# VF_MDS_PCB.net
KiCad netlist of a schematic drawn in EAGLE
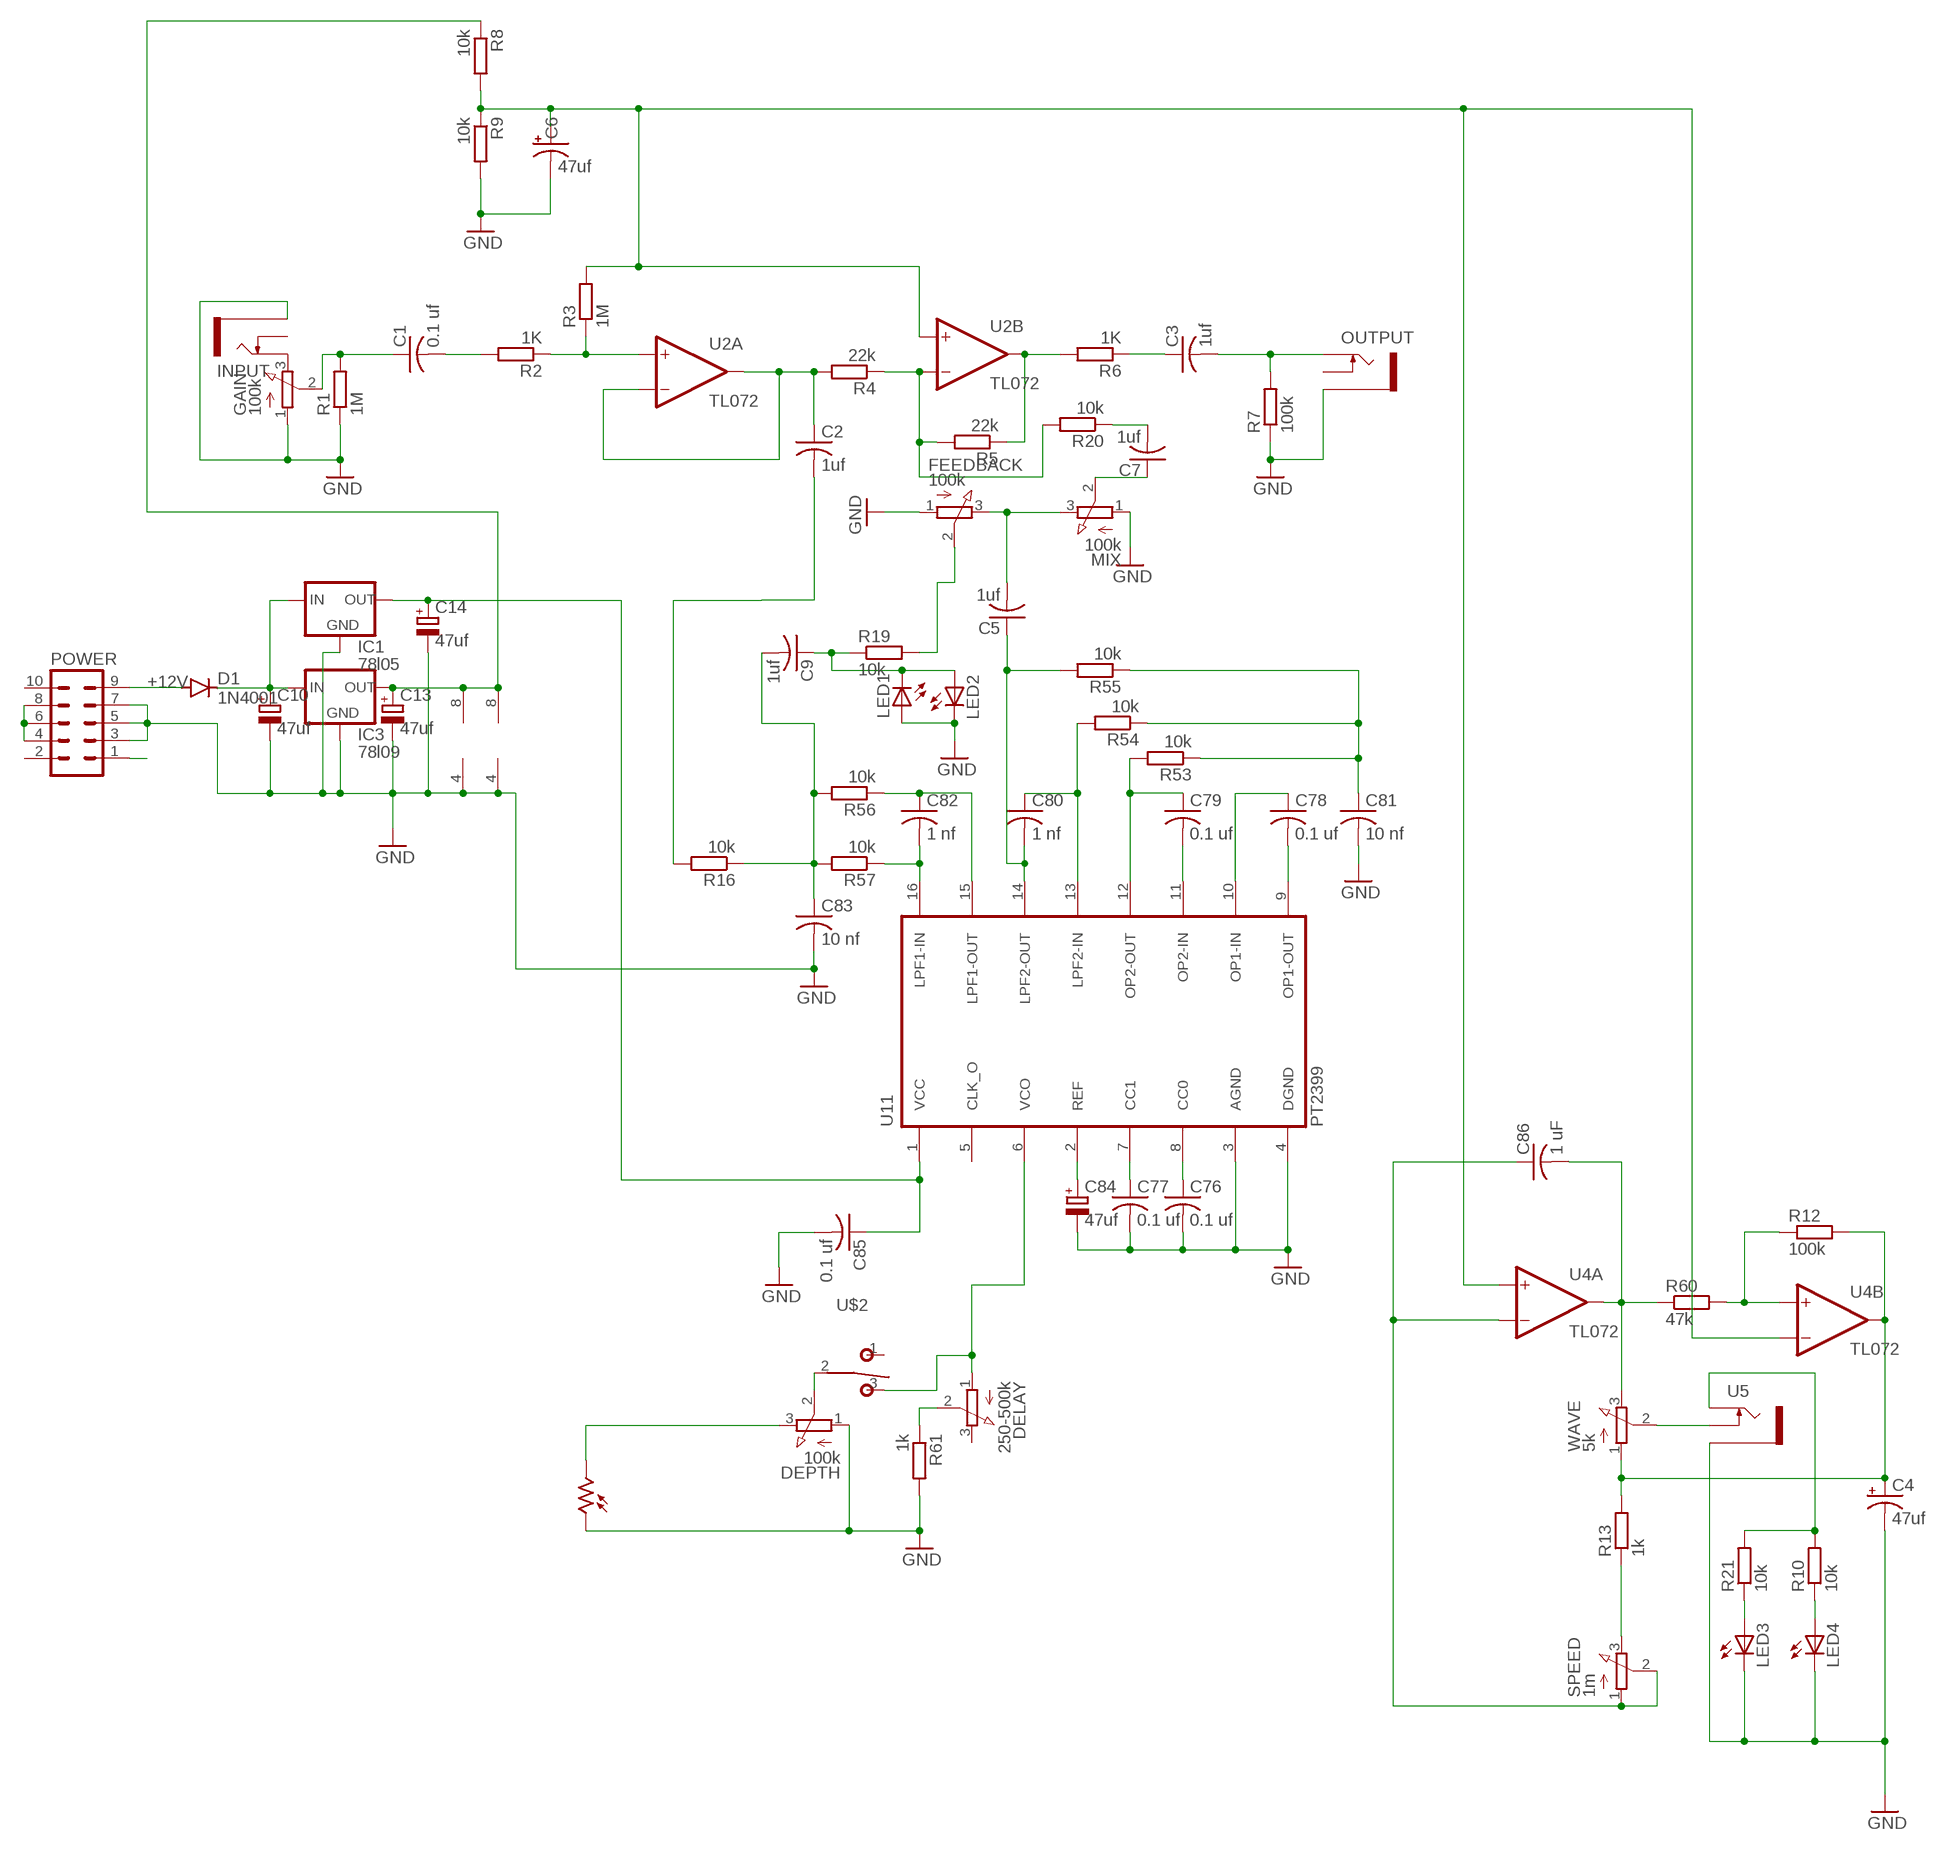
[diagram p0: schematic, sheet 1]

(export (version "E")
  (design (tool "Eeschema 10.0.6"))
  (components
    (comp (ref "C1")
      (value "0.1 uf")
      (footprint "eagle-import:C050-025X075")
      (libsource (lib "eagle-import") (part "C-US050-025X075"))
    )
    (comp (ref "C2")
      (value "1uf")
      (footprint "eagle-import:C050-025X075")
      (libsource (lib "eagle-import") (part "C-US050-025X075"))
    )
    (comp (ref "C3")
      (value "1uf")
      (footprint "eagle-import:C050-025X075")
      (libsource (lib "eagle-import") (part "C-US050-025X075"))
    )
    (comp (ref "C4")
      (value "47uf")
      (footprint "eagle-import:E2,5-6E")
      (libsource (lib "eagle-import") (part "CPOL-USE2,5-6E"))
    )
    (comp (ref "C5")
      (value "1uf")
      (footprint "eagle-import:C050-025X075")
      (libsource (lib "eagle-import") (part "C-US050-025X075"))
    )
    (comp (ref "C6")
      (value "47uf")
      (footprint "eagle-import:E2,5-6E")
      (libsource (lib "eagle-import") (part "CPOL-USE2,5-6E"))
    )
    (comp (ref "C7")
      (value "1uf")
      (footprint "eagle-import:C050-025X075")
      (libsource (lib "eagle-import") (part "C-US050-025X075"))
    )
    (comp (ref "C9")
      (value "1uf")
      (footprint "eagle-import:C050-025X075")
      (libsource (lib "eagle-import") (part "C-US050-025X075"))
    )
    (comp (ref "C10")
      (value "47uf")
      (footprint "eagle-import:E2,5-6E")
      (libsource (lib "eagle-import") (part "CPOL-EUE2,5-6E"))
    )
    (comp (ref "C13")
      (value "47uf")
      (footprint "eagle-import:E2,5-6E")
      (libsource (lib "eagle-import") (part "CPOL-EUE2,5-6E"))
    )
    (comp (ref "C14")
      (value "47uf")
      (footprint "eagle-import:E2,5-6E")
      (libsource (lib "eagle-import") (part "CPOL-EUE2,5-6E"))
    )
    (comp (ref "C76")
      (value "0.1 uf")
      (footprint "eagle-import:C050-025X075")
      (libsource (lib "eagle-import") (part "C-US050-025X075"))
    )
    (comp (ref "C77")
      (value "0.1 uf")
      (footprint "eagle-import:C050-025X075")
      (libsource (lib "eagle-import") (part "C-US050-025X075"))
    )
    (comp (ref "C78")
      (value "0.1 uf")
      (footprint "eagle-import:C050-025X075")
      (libsource (lib "eagle-import") (part "C-US050-025X075"))
    )
    (comp (ref "C79")
      (value "0.1 uf")
      (footprint "eagle-import:C050-025X075")
      (libsource (lib "eagle-import") (part "C-US050-025X075"))
    )
    (comp (ref "C80")
      (value "1 nf")
      (footprint "eagle-import:C050-025X075")
      (libsource (lib "eagle-import") (part "C-US050-025X075"))
    )
    (comp (ref "C81")
      (value "10 nf")
      (footprint "eagle-import:C050-025X075")
      (libsource (lib "eagle-import") (part "C-US050-025X075"))
    )
    (comp (ref "C82")
      (value "1 nf")
      (footprint "eagle-import:C050-025X075")
      (libsource (lib "eagle-import") (part "C-US050-025X075"))
    )
    (comp (ref "C83")
      (value "10 nf")
      (footprint "eagle-import:C050-025X075")
      (libsource (lib "eagle-import") (part "C-US050-025X075"))
    )
    (comp (ref "C84")
      (value "47uf")
      (footprint "eagle-import:E2,5-6E")
      (libsource (lib "eagle-import") (part "CPOL-EUE2,5-6E"))
    )
    (comp (ref "C85")
      (value "0.1 uf")
      (footprint "eagle-import:C050-025X075")
      (libsource (lib "eagle-import") (part "C-US050-025X075"))
    )
    (comp (ref "C86")
      (value "1 uF")
      (footprint "eagle-import:C050-025X075")
      (libsource (lib "eagle-import") (part "C-US050-025X075"))
    )
    (comp (ref "D1")
      (value "1N4001")
      (footprint "eagle-import:DO41-10")
      (libsource (lib "eagle-import") (part "1N4004"))
    )
    (comp (ref "DELAY")
      (value "250-500k")
      (footprint "eagle-import:EVUFXL")
      (libsource (lib "eagle-import") (part "EVULF2"))
    )
    (comp (ref "DEPTH")
      (value "100k")
      (footprint "eagle-import:EVUFXL")
      (libsource (lib "eagle-import") (part "EVULF2"))
    )
    (comp (ref "FEEDBACK")
      (value "100k")
      (footprint "eagle-import:EVUFXL")
      (libsource (lib "eagle-import") (part "EVULF2"))
    )
    (comp (ref "GAIN")
      (value "100k")
      (footprint "eagle-import:EVUFXL")
      (libsource (lib "eagle-import") (part "EVULF2"))
    )
    (comp (ref "IC1")
      (value "78l05")
      (footprint "eagle-import:78LXX")
      (libsource (lib "eagle-import") (part "78LXX"))
    )
    (comp (ref "IC3")
      (value "78l09")
      (footprint "eagle-import:78LXX")
      (libsource (lib "eagle-import") (part "78LXX"))
    )
    (comp (ref "INPUT")
      (value "THONKICONNNEW")
      (footprint "eagle-import:WQP-PJ301M-12_JACK")
      (libsource (lib "eagle-import") (part "THONKICONNNEW"))
    )
    (comp (ref "LED1")
      (value "LED3MM")
      (footprint "eagle-import:LED3MM")
      (libsource (lib "eagle-import") (part "LED3MM"))
    )
    (comp (ref "LED2")
      (value "LED3MM")
      (footprint "eagle-import:LED3MM")
      (libsource (lib "eagle-import") (part "LED3MM"))
    )
    (comp (ref "LED3")
      (value "LED5MM")
      (footprint "eagle-import:LED5MM")
      (libsource (lib "eagle-import") (part "LED5MM"))
    )
    (comp (ref "LED4")
      (value "LED5MM")
      (footprint "eagle-import:LED5MM")
      (libsource (lib "eagle-import") (part "LED5MM"))
    )
    (comp (ref "MIX")
      (value "100k")
      (footprint "eagle-import:EVUFXL")
      (libsource (lib "eagle-import") (part "EVULF2"))
    )
    (comp (ref "OUTPUT")
      (value "THONKICONNNEW")
      (footprint "eagle-import:WQP-PJ301M-12_JACK")
      (libsource (lib "eagle-import") (part "THONKICONNNEW"))
    )
    (comp (ref "PH5")
      (value "VT90N1")
      (footprint "eagle-import:VT900")
      (libsource (lib "eagle-import") (part "VT90N1"))
    )
    (comp (ref "POWER")
      (value "10_PIN_HEADER")
      (footprint "eagle-import:MA05-2")
      (libsource (lib "eagle-import") (part "10_PIN_HEADER"))
    )
    (comp (ref "R1")
      (value "1M")
      (footprint "eagle-import:7MM_RESISTOR")
      (libsource (lib "eagle-import") (part "RESISTOR7MM"))
    )
    (comp (ref "R2")
      (value "1K")
      (footprint "eagle-import:7MM_RESISTOR")
      (libsource (lib "eagle-import") (part "RESISTOR7MM"))
    )
    (comp (ref "R3")
      (value "1M")
      (footprint "eagle-import:7MM_RESISTOR")
      (libsource (lib "eagle-import") (part "RESISTOR7MM"))
    )
    (comp (ref "R4")
      (value "22k")
      (footprint "eagle-import:7MM_RESISTOR")
      (libsource (lib "eagle-import") (part "RESISTOR7MM"))
    )
    (comp (ref "R5")
      (value "22k")
      (footprint "eagle-import:7MM_RESISTOR")
      (libsource (lib "eagle-import") (part "RESISTOR7MM"))
    )
    (comp (ref "R6")
      (value "1K")
      (footprint "eagle-import:7MM_RESISTOR")
      (libsource (lib "eagle-import") (part "RESISTOR7MM"))
    )
    (comp (ref "R7")
      (value "100k")
      (footprint "eagle-import:7MM_RESISTOR")
      (libsource (lib "eagle-import") (part "RESISTOR7MM"))
    )
    (comp (ref "R8")
      (value "10k")
      (footprint "eagle-import:7MM_RESISTOR")
      (libsource (lib "eagle-import") (part "RESISTOR7MM"))
    )
    (comp (ref "R9")
      (value "10k")
      (footprint "eagle-import:7MM_RESISTOR")
      (libsource (lib "eagle-import") (part "RESISTOR7MM"))
    )
    (comp (ref "R10")
      (value "10k")
      (footprint "eagle-import:7MM_RESISTOR")
      (libsource (lib "eagle-import") (part "RESISTOR7MM"))
    )
    (comp (ref "R12")
      (value "100k")
      (footprint "eagle-import:7MM_RESISTOR")
      (libsource (lib "eagle-import") (part "RESISTOR7MM"))
    )
    (comp (ref "R13")
      (value "1k")
      (footprint "eagle-import:7MM_RESISTOR")
      (libsource (lib "eagle-import") (part "RESISTOR7MM"))
    )
    (comp (ref "R16")
      (value "10k")
      (footprint "eagle-import:7MM_RESISTOR")
      (libsource (lib "eagle-import") (part "RESISTOR7MM"))
    )
    (comp (ref "R19")
      (value "10k")
      (footprint "eagle-import:7MM_RESISTOR")
      (libsource (lib "eagle-import") (part "RESISTOR7MM"))
    )
    (comp (ref "R20")
      (value "10k")
      (footprint "eagle-import:7MM_RESISTOR")
      (libsource (lib "eagle-import") (part "RESISTOR7MM"))
    )
    (comp (ref "R21")
      (value "10k")
      (footprint "eagle-import:7MM_RESISTOR")
      (libsource (lib "eagle-import") (part "RESISTOR7MM"))
    )
    (comp (ref "R53")
      (value "10k")
      (footprint "eagle-import:7MM_RESISTOR")
      (libsource (lib "eagle-import") (part "RESISTOR7MM"))
    )
    (comp (ref "R54")
      (value "10k")
      (footprint "eagle-import:7MM_RESISTOR")
      (libsource (lib "eagle-import") (part "RESISTOR7MM"))
    )
    (comp (ref "R55")
      (value "10k")
      (footprint "eagle-import:7MM_RESISTOR")
      (libsource (lib "eagle-import") (part "RESISTOR7MM"))
    )
    (comp (ref "R56")
      (value "10k")
      (footprint "eagle-import:7MM_RESISTOR")
      (libsource (lib "eagle-import") (part "RESISTOR7MM"))
    )
    (comp (ref "R57")
      (value "10k")
      (footprint "eagle-import:7MM_RESISTOR")
      (libsource (lib "eagle-import") (part "RESISTOR7MM"))
    )
    (comp (ref "R60")
      (value "47k")
      (footprint "eagle-import:7MM_RESISTOR")
      (libsource (lib "eagle-import") (part "RESISTOR7MM"))
    )
    (comp (ref "R61")
      (value "1k")
      (footprint "eagle-import:7MM_RESISTOR")
      (libsource (lib "eagle-import") (part "RESISTOR7MM"))
    )
    (comp (ref "SPEED")
      (value "1m")
      (footprint "eagle-import:EVUFXL")
      (libsource (lib "eagle-import") (part "EVULF2"))
    )
    (comp (ref "U$2")
      (value "T-80-T-SPDT-ON-OFF-ON")
      (footprint "eagle-import:M9040P")
      (libsource (lib "eagle-import") (part "T-80-T-SPDT-ON-OFF-ON"))
    )
    (comp (ref "U2")
      (value "TL072")
      (footprint "eagle-import:DIL08-SML")
      (libsource (lib "eagle-import") (part "TL072"))
    )
    (comp (ref "U4")
      (value "TL072")
      (footprint "eagle-import:DIL08-SML")
      (libsource (lib "eagle-import") (part "TL072"))
    )
    (comp (ref "U5")
      (value "THONKICONNNEW")
      (footprint "eagle-import:WQP-PJ301M-12_JACK")
      (libsource (lib "eagle-import") (part "THONKICONNNEW"))
    )
    (comp (ref "U11")
      (value "PT2399")
      (footprint "eagle-import:DIL16")
      (libsource (lib "eagle-import") (part "PT2399"))
    )
    (comp (ref "WAVE")
      (value "5k")
      (footprint "eagle-import:EVUFXL")
      (libsource (lib "eagle-import") (part "EVULF2"))
    )
  )
  (nets
    (net (code "1") (name "/+12V") (class "Default")
      (node (ref "C10") (pin "+") (pinfunction "+_+") (pintype "passive"))
      (node (ref "D1") (pin "C") (pinfunction "C_C") (pintype "passive"))
      (node (ref "IC1") (pin "IN") (pinfunction "IN_IN") (pintype "input"))
      (node (ref "IC3") (pin "IN") (pinfunction "IN_IN") (pintype "input"))
    )
    (net (code "2") (name "GND") (class "Default")
      (node (ref "C10") (pin "-") (pinfunction "-_-") (pintype "passive"))
      (node (ref "C13") (pin "-") (pinfunction "-_-") (pintype "passive"))
      (node (ref "C14") (pin "-") (pinfunction "-_-") (pintype "passive"))
      (node (ref "C4") (pin "-") (pinfunction "-_-") (pintype "passive"))
      (node (ref "C6") (pin "-") (pinfunction "-_-") (pintype "passive"))
      (node (ref "C76") (pin "2") (pinfunction "2_2") (pintype "passive"))
      (node (ref "C77") (pin "2") (pinfunction "2_2") (pintype "passive"))
      (node (ref "C81") (pin "2") (pinfunction "2_2") (pintype "passive"))
      (node (ref "C83") (pin "2") (pinfunction "2_2") (pintype "passive"))
      (node (ref "C84") (pin "-") (pinfunction "-_-") (pintype "passive"))
      (node (ref "C85") (pin "2") (pinfunction "2_2") (pintype "passive"))
      (node (ref "DEPTH") (pin "1") (pinfunction "A_1") (pintype "passive"))
      (node (ref "FEEDBACK") (pin "1") (pinfunction "A_1") (pintype "passive"))
      (node (ref "GAIN") (pin "1") (pinfunction "A_1") (pintype "passive"))
      (node (ref "IC1") (pin "GND") (pinfunction "GND_GND") (pintype "input"))
      (node (ref "IC3") (pin "GND") (pinfunction "GND_GND") (pintype "input"))
      (node (ref "INPUT") (pin "P$3_SLEEVE") (pinfunction "SLEEVE_P$3_SLEEVE") (pintype "passive"))
      (node (ref "LED1") (pin "A") (pinfunction "A_A") (pintype "passive"))
      (node (ref "LED2") (pin "K") (pinfunction "C_K") (pintype "passive"))
      (node (ref "LED3") (pin "K") (pinfunction "C_K") (pintype "passive"))
      (node (ref "LED4") (pin "K") (pinfunction "C_K") (pintype "passive"))
      (node (ref "MIX") (pin "1") (pinfunction "A_1") (pintype "passive"))
      (node (ref "OUTPUT") (pin "P$3_SLEEVE") (pinfunction "SLEEVE_P$3_SLEEVE") (pintype "passive"))
      (node (ref "PH5") (pin "1") (pinfunction "1_1") (pintype "passive"))
      (node (ref "POWER") (pin "3") (pinfunction "3_3") (pintype "passive"))
      (node (ref "POWER") (pin "5") (pinfunction "5_5") (pintype "passive"))
      (node (ref "POWER") (pin "7") (pinfunction "7_7") (pintype "passive"))
      (node (ref "R1") (pin "1") (pinfunction "1_1") (pintype "passive"))
      (node (ref "R61") (pin "2") (pinfunction "2_2") (pintype "passive"))
      (node (ref "R7") (pin "1") (pinfunction "1_1") (pintype "passive"))
      (node (ref "R9") (pin "2") (pinfunction "2_2") (pintype "passive"))
      (node (ref "U11") (pin "3") (pinfunction "AGND_3") (pintype "power_in"))
      (node (ref "U11") (pin "4") (pinfunction "DGND_4") (pintype "power_in"))
      (node (ref "U2") (pin "4") (pinfunction "V-_4") (pintype "power_in"))
      (node (ref "U4") (pin "4") (pinfunction "V-_4") (pintype "power_in"))
      (node (ref "U5") (pin "P$3_SLEEVE") (pinfunction "SLEEVE_P$3_SLEEVE") (pintype "passive"))
    )
    (net (code "3") (name "Net-(C1-Pad2)") (class "Default")
      (node (ref "C1") (pin "2") (pinfunction "2_2") (pintype "passive"))
      (node (ref "R2") (pin "2") (pinfunction "2_2") (pintype "passive"))
    )
    (net (code "4") (name "Net-(C2-Pad2)") (class "Default")
      (node (ref "C2") (pin "2") (pinfunction "2_2") (pintype "passive"))
      (node (ref "R16") (pin "2") (pinfunction "2_2") (pintype "passive"))
    )
    (net (code "5") (name "Net-(C3-Pad1)") (class "Default")
      (node (ref "C3") (pin "1") (pinfunction "1_1") (pintype "passive"))
      (node (ref "R6") (pin "1") (pinfunction "1_1") (pintype "passive"))
    )
    (net (code "6") (name "Net-(C7-Pad2)") (class "Default")
      (node (ref "C7") (pin "2") (pinfunction "2_2") (pintype "passive"))
      (node (ref "R20") (pin "1") (pinfunction "1_1") (pintype "passive"))
    )
    (net (code "7") (name "Net-(C81-Pad1)") (class "Default")
      (node (ref "C81") (pin "1") (pinfunction "1_1") (pintype "passive"))
      (node (ref "R53") (pin "1") (pinfunction "1_1") (pintype "passive"))
      (node (ref "R54") (pin "1") (pinfunction "1_1") (pintype "passive"))
      (node (ref "R55") (pin "1") (pinfunction "1_1") (pintype "passive"))
    )
    (net (code "8") (name "Net-(C83-Pad1)") (class "Default")
      (node (ref "C83") (pin "1") (pinfunction "1_1") (pintype "passive"))
      (node (ref "C9") (pin "2") (pinfunction "2_2") (pintype "passive"))
      (node (ref "R16") (pin "1") (pinfunction "1_1") (pintype "passive"))
      (node (ref "R56") (pin "2") (pinfunction "2_2") (pintype "passive"))
      (node (ref "R57") (pin "2") (pinfunction "2_2") (pintype "passive"))
    )
    (net (code "9") (name "Net-(D1-PadA)") (class "Default")
      (node (ref "D1") (pin "A") (pinfunction "A_A") (pintype "passive"))
      (node (ref "POWER") (pin "9") (pinfunction "9_9") (pintype "passive"))
    )
    (net (code "10") (name "Net-(DELAY-A)") (class "Default")
      (node (ref "DELAY") (pin "1") (pinfunction "A_1") (pintype "passive"))
      (node (ref "U$2") (pin "3") (pinfunction "S_3") (pintype "passive"))
      (node (ref "U11") (pin "6") (pinfunction "VCO_6") (pintype "input"))
    )
    (net (code "11") (name "Net-(DELAY-S)") (class "Default")
      (node (ref "DELAY") (pin "2") (pinfunction "S_2") (pintype "passive"))
      (node (ref "R61") (pin "1") (pinfunction "1_1") (pintype "passive"))
    )
    (net (code "12") (name "Net-(DEPTH-E)") (class "Default")
      (node (ref "DEPTH") (pin "3") (pinfunction "E_3") (pintype "passive"))
      (node (ref "PH5") (pin "2") (pinfunction "2_2") (pintype "passive"))
    )
    (net (code "13") (name "Net-(DEPTH-S)") (class "Default")
      (node (ref "DEPTH") (pin "2") (pinfunction "S_2") (pintype "passive"))
      (node (ref "U$2") (pin "2") (pinfunction "P_2") (pintype "passive"))
    )
    (net (code "14") (name "Net-(FEEDBACK-E)") (class "Default")
      (node (ref "C5") (pin "2") (pinfunction "2_2") (pintype "passive"))
      (node (ref "FEEDBACK") (pin "3") (pinfunction "E_3") (pintype "passive"))
      (node (ref "MIX") (pin "3") (pinfunction "E_3") (pintype "passive"))
    )
    (net (code "15") (name "Net-(FEEDBACK-S)") (class "Default")
      (node (ref "FEEDBACK") (pin "2") (pinfunction "S_2") (pintype "passive"))
      (node (ref "R19") (pin "2") (pinfunction "2_2") (pintype "passive"))
    )
    (net (code "16") (name "Net-(GAIN-E)") (class "Default")
      (node (ref "GAIN") (pin "3") (pinfunction "E_3") (pintype "passive"))
      (node (ref "INPUT") (pin "P$1_TIP") (pinfunction "TIP_P$1_TIP") (pintype "passive"))
    )
    (net (code "17") (name "Net-(GAIN-S)") (class "Default")
      (node (ref "C1") (pin "1") (pinfunction "1_1") (pintype "passive"))
      (node (ref "GAIN") (pin "2") (pinfunction "S_2") (pintype "passive"))
      (node (ref "R1") (pin "2") (pinfunction "2_2") (pintype "passive"))
    )
    (net (code "18") (name "Net-(LED1-C)") (class "Default")
      (node (ref "C9") (pin "1") (pinfunction "1_1") (pintype "passive"))
      (node (ref "LED1") (pin "K") (pinfunction "C_K") (pintype "passive"))
      (node (ref "LED2") (pin "A") (pinfunction "A_A") (pintype "passive"))
      (node (ref "R19") (pin "1") (pinfunction "1_1") (pintype "passive"))
    )
    (net (code "19") (name "Net-(LED3-PadA)") (class "Default")
      (node (ref "LED3") (pin "A") (pinfunction "A_A") (pintype "passive"))
      (node (ref "R21") (pin "1") (pinfunction "1_1") (pintype "passive"))
    )
    (net (code "20") (name "Net-(LED4-PadA)") (class "Default")
      (node (ref "LED4") (pin "A") (pinfunction "A_A") (pintype "passive"))
      (node (ref "R10") (pin "1") (pinfunction "1_1") (pintype "passive"))
    )
    (net (code "21") (name "Net-(MIX-S)") (class "Default")
      (node (ref "C7") (pin "1") (pinfunction "1_1") (pintype "passive"))
      (node (ref "MIX") (pin "2") (pinfunction "S_2") (pintype "passive"))
    )
    (net (code "22") (name "Net-(OUTPUT-TIP)") (class "Default")
      (node (ref "C3") (pin "2") (pinfunction "2_2") (pintype "passive"))
      (node (ref "OUTPUT") (pin "P$1_TIP") (pinfunction "TIP_P$1_TIP") (pintype "passive"))
      (node (ref "R7") (pin "2") (pinfunction "2_2") (pintype "passive"))
    )
    (net (code "23") (name "Net-(POWER-Pad4)") (class "Default")
      (node (ref "POWER") (pin "4") (pinfunction "4_4") (pintype "passive"))
      (node (ref "POWER") (pin "6") (pinfunction "6_6") (pintype "passive"))
      (node (ref "POWER") (pin "8") (pinfunction "8_8") (pintype "passive"))
    )
    (net (code "24") (name "Net-(SPEED-A)") (class "Default")
      (node (ref "C86") (pin "1") (pinfunction "1_1") (pintype "passive"))
      (node (ref "SPEED") (pin "1") (pinfunction "A_1") (pintype "passive"))
      (node (ref "SPEED") (pin "2") (pinfunction "S_2") (pintype "passive"))
      (node (ref "U4") (pin "2") (pinfunction "-IN_2") (pintype "input"))
    )
    (net (code "25") (name "Net-(SPEED-E)") (class "Default")
      (node (ref "R13") (pin "1") (pinfunction "1_1") (pintype "passive"))
      (node (ref "SPEED") (pin "3") (pinfunction "E_3") (pintype "passive"))
    )
    (net (code "26") (name "Net-(U2A-+IN)") (class "Default")
      (node (ref "R2") (pin "1") (pinfunction "1_1") (pintype "passive"))
      (node (ref "R3") (pin "1") (pinfunction "1_1") (pintype "passive"))
      (node (ref "U2") (pin "3") (pinfunction "+IN_3") (pintype "input"))
    )
    (net (code "27") (name "Net-(U2A--IN)") (class "Default")
      (node (ref "C2") (pin "1") (pinfunction "1_1") (pintype "passive"))
      (node (ref "R4") (pin "2") (pinfunction "2_2") (pintype "passive"))
      (node (ref "U2") (pin "1") (pinfunction "OUT_1") (pintype "output"))
      (node (ref "U2") (pin "2") (pinfunction "-IN_2") (pintype "input"))
    )
    (net (code "28") (name "Net-(U2B-+IN)") (class "Default")
      (node (ref "C6") (pin "+") (pinfunction "+_+") (pintype "passive"))
      (node (ref "R3") (pin "2") (pinfunction "2_2") (pintype "passive"))
      (node (ref "R8") (pin "2") (pinfunction "2_2") (pintype "passive"))
      (node (ref "R9") (pin "1") (pinfunction "1_1") (pintype "passive"))
      (node (ref "U2") (pin "5") (pinfunction "+IN_5") (pintype "input"))
      (node (ref "U4") (pin "3") (pinfunction "+IN_3") (pintype "input"))
      (node (ref "U4") (pin "6") (pinfunction "-IN_6") (pintype "input"))
    )
    (net (code "29") (name "Net-(U2B--IN)") (class "Default")
      (node (ref "R20") (pin "2") (pinfunction "2_2") (pintype "passive"))
      (node (ref "R4") (pin "1") (pinfunction "1_1") (pintype "passive"))
      (node (ref "R5") (pin "2") (pinfunction "2_2") (pintype "passive"))
      (node (ref "U2") (pin "6") (pinfunction "-IN_6") (pintype "input"))
    )
    (net (code "30") (name "Net-(U2B-OUT)") (class "Default")
      (node (ref "R5") (pin "1") (pinfunction "1_1") (pintype "passive"))
      (node (ref "R6") (pin "2") (pinfunction "2_2") (pintype "passive"))
      (node (ref "U2") (pin "7") (pinfunction "OUT_7") (pintype "output"))
    )
    (net (code "31") (name "Net-(U2C-V+)") (class "Default")
      (node (ref "C13") (pin "+") (pinfunction "+_+") (pintype "passive"))
      (node (ref "IC3") (pin "OUT") (pinfunction "OUT_OUT") (pintype "passive"))
      (node (ref "R8") (pin "1") (pinfunction "1_1") (pintype "passive"))
      (node (ref "U2") (pin "8") (pinfunction "V+_8") (pintype "power_in"))
      (node (ref "U4") (pin "8") (pinfunction "V+_8") (pintype "power_in"))
    )
    (net (code "32") (name "Net-(U4A-OUT)") (class "Default")
      (node (ref "C86") (pin "2") (pinfunction "2_2") (pintype "passive"))
      (node (ref "R60") (pin "1") (pinfunction "1_1") (pintype "passive"))
      (node (ref "U4") (pin "1") (pinfunction "OUT_1") (pintype "output"))
      (node (ref "WAVE") (pin "3") (pinfunction "E_3") (pintype "passive"))
    )
    (net (code "33") (name "Net-(U4B-+IN)") (class "Default")
      (node (ref "R12") (pin "1") (pinfunction "1_1") (pintype "passive"))
      (node (ref "R60") (pin "2") (pinfunction "2_2") (pintype "passive"))
      (node (ref "U4") (pin "5") (pinfunction "+IN_5") (pintype "input"))
    )
    (net (code "34") (name "Net-(U4B-OUT)") (class "Default")
      (node (ref "C4") (pin "+") (pinfunction "+_+") (pintype "passive"))
      (node (ref "R12") (pin "2") (pinfunction "2_2") (pintype "passive"))
      (node (ref "R13") (pin "2") (pinfunction "2_2") (pintype "passive"))
      (node (ref "U4") (pin "7") (pinfunction "OUT_7") (pintype "output"))
      (node (ref "WAVE") (pin "1") (pinfunction "A_1") (pintype "passive"))
    )
    (net (code "35") (name "Net-(U5-SWITCH)") (class "Default")
      (node (ref "U5") (pin "P$2_SWITCH") (pinfunction "SWITCH_P$2_SWITCH") (pintype "passive"))
      (node (ref "WAVE") (pin "2") (pinfunction "S_2") (pintype "passive"))
    )
    (net (code "36") (name "Net-(U5-TIP)") (class "Default")
      (node (ref "R10") (pin "2") (pinfunction "2_2") (pintype "passive"))
      (node (ref "R21") (pin "2") (pinfunction "2_2") (pintype "passive"))
      (node (ref "U5") (pin "P$1_TIP") (pinfunction "TIP_P$1_TIP") (pintype "passive"))
    )
    (net (code "37") (name "Net-(U11-CC0)") (class "Default")
      (node (ref "C76") (pin "1") (pinfunction "1_1") (pintype "passive"))
      (node (ref "U11") (pin "8") (pinfunction "CC0_8") (pintype "input"))
    )
    (net (code "38") (name "Net-(U11-CC1)") (class "Default")
      (node (ref "C77") (pin "1") (pinfunction "1_1") (pintype "passive"))
      (node (ref "U11") (pin "7") (pinfunction "CC1_7") (pintype "input"))
    )
    (net (code "39") (name "Net-(U11-LPF1-IN)") (class "Default")
      (node (ref "C82") (pin "2") (pinfunction "2_2") (pintype "passive"))
      (node (ref "R57") (pin "1") (pinfunction "1_1") (pintype "passive"))
      (node (ref "U11") (pin "16") (pinfunction "LPF1-IN_16") (pintype "input"))
    )
    (net (code "40") (name "Net-(U11-LPF1-OUT)") (class "Default")
      (node (ref "C82") (pin "1") (pinfunction "1_1") (pintype "passive"))
      (node (ref "R56") (pin "1") (pinfunction "1_1") (pintype "passive"))
      (node (ref "U11") (pin "15") (pinfunction "LPF1-OUT_15") (pintype "output"))
    )
    (net (code "41") (name "Net-(U11-LPF2-IN)") (class "Default")
      (node (ref "C80") (pin "1") (pinfunction "1_1") (pintype "passive"))
      (node (ref "R54") (pin "2") (pinfunction "2_2") (pintype "passive"))
      (node (ref "U11") (pin "13") (pinfunction "LPF2-IN_13") (pintype "input"))
    )
    (net (code "42") (name "Net-(U11-LPF2-OUT)") (class "Default")
      (node (ref "C5") (pin "1") (pinfunction "1_1") (pintype "passive"))
      (node (ref "C80") (pin "2") (pinfunction "2_2") (pintype "passive"))
      (node (ref "R55") (pin "2") (pinfunction "2_2") (pintype "passive"))
      (node (ref "U11") (pin "14") (pinfunction "LPF2-OUT_14") (pintype "output"))
    )
    (net (code "43") (name "Net-(U11-OP1-IN)") (class "Default")
      (node (ref "C78") (pin "1") (pinfunction "1_1") (pintype "passive"))
      (node (ref "U11") (pin "10") (pinfunction "OP1-IN_10") (pintype "input"))
    )
    (net (code "44") (name "Net-(U11-OP1-OUT)") (class "Default")
      (node (ref "C78") (pin "2") (pinfunction "2_2") (pintype "passive"))
      (node (ref "U11") (pin "9") (pinfunction "OP1-OUT_9") (pintype "output"))
    )
    (net (code "45") (name "Net-(U11-OP2-IN)") (class "Default")
      (node (ref "C79") (pin "2") (pinfunction "2_2") (pintype "passive"))
      (node (ref "U11") (pin "11") (pinfunction "OP2-IN_11") (pintype "input"))
    )
    (net (code "46") (name "Net-(U11-OP2-OUT)") (class "Default")
      (node (ref "C79") (pin "1") (pinfunction "1_1") (pintype "passive"))
      (node (ref "R53") (pin "2") (pinfunction "2_2") (pintype "passive"))
      (node (ref "U11") (pin "12") (pinfunction "OP2-OUT_12") (pintype "output"))
    )
    (net (code "47") (name "Net-(U11-REF)") (class "Default")
      (node (ref "C84") (pin "+") (pinfunction "+_+") (pintype "passive"))
      (node (ref "U11") (pin "2") (pinfunction "REF_2") (pintype "input"))
    )
    (net (code "48") (name "Net-(U11-VCC)") (class "Default")
      (node (ref "C14") (pin "+") (pinfunction "+_+") (pintype "passive"))
      (node (ref "C85") (pin "1") (pinfunction "1_1") (pintype "passive"))
      (node (ref "IC1") (pin "OUT") (pinfunction "OUT_OUT") (pintype "passive"))
      (node (ref "U11") (pin "1") (pinfunction "VCC_1") (pintype "power_in"))
    )
    (net (code "49") (name "unconnected-(DELAY-E-Pad3)") (class "Default")
      (node (ref "DELAY") (pin "3") (pinfunction "E_3") (pintype "passive"))
    )
    (net (code "50") (name "unconnected-(INPUT-SWITCH-PadP$2_SWITCH)") (class "Default")
      (node (ref "INPUT") (pin "P$2_SWITCH") (pinfunction "SWITCH_P$2_SWITCH") (pintype "passive"))
    )
    (net (code "51") (name "unconnected-(OUTPUT-SWITCH-PadP$2_SWITCH)") (class "Default")
      (node (ref "OUTPUT") (pin "P$2_SWITCH") (pinfunction "SWITCH_P$2_SWITCH") (pintype "passive"))
    )
    (net (code "52") (name "unconnected-(POWER-Pad1)") (class "Default")
      (node (ref "POWER") (pin "1") (pinfunction "1_1") (pintype "passive"))
    )
    (net (code "53") (name "unconnected-(POWER-Pad2)") (class "Default")
      (node (ref "POWER") (pin "2") (pinfunction "2_2") (pintype "passive"))
    )
    (net (code "54") (name "unconnected-(POWER-Pad10)") (class "Default")
      (node (ref "POWER") (pin "10") (pinfunction "10_10") (pintype "passive"))
    )
    (net (code "55") (name "unconnected-(U$2-O-Pad1)") (class "Default")
      (node (ref "U$2") (pin "1") (pinfunction "O_1") (pintype "passive"))
    )
    (net (code "56") (name "unconnected-(U11-CLK_O-Pad5)") (class "Default")
      (node (ref "U11") (pin "5") (pinfunction "CLK_O_5") (pintype "output"))
    )
  )
)
